# Relay_IO.net
KiCad netlist of a schematic drawn in Altium Designer
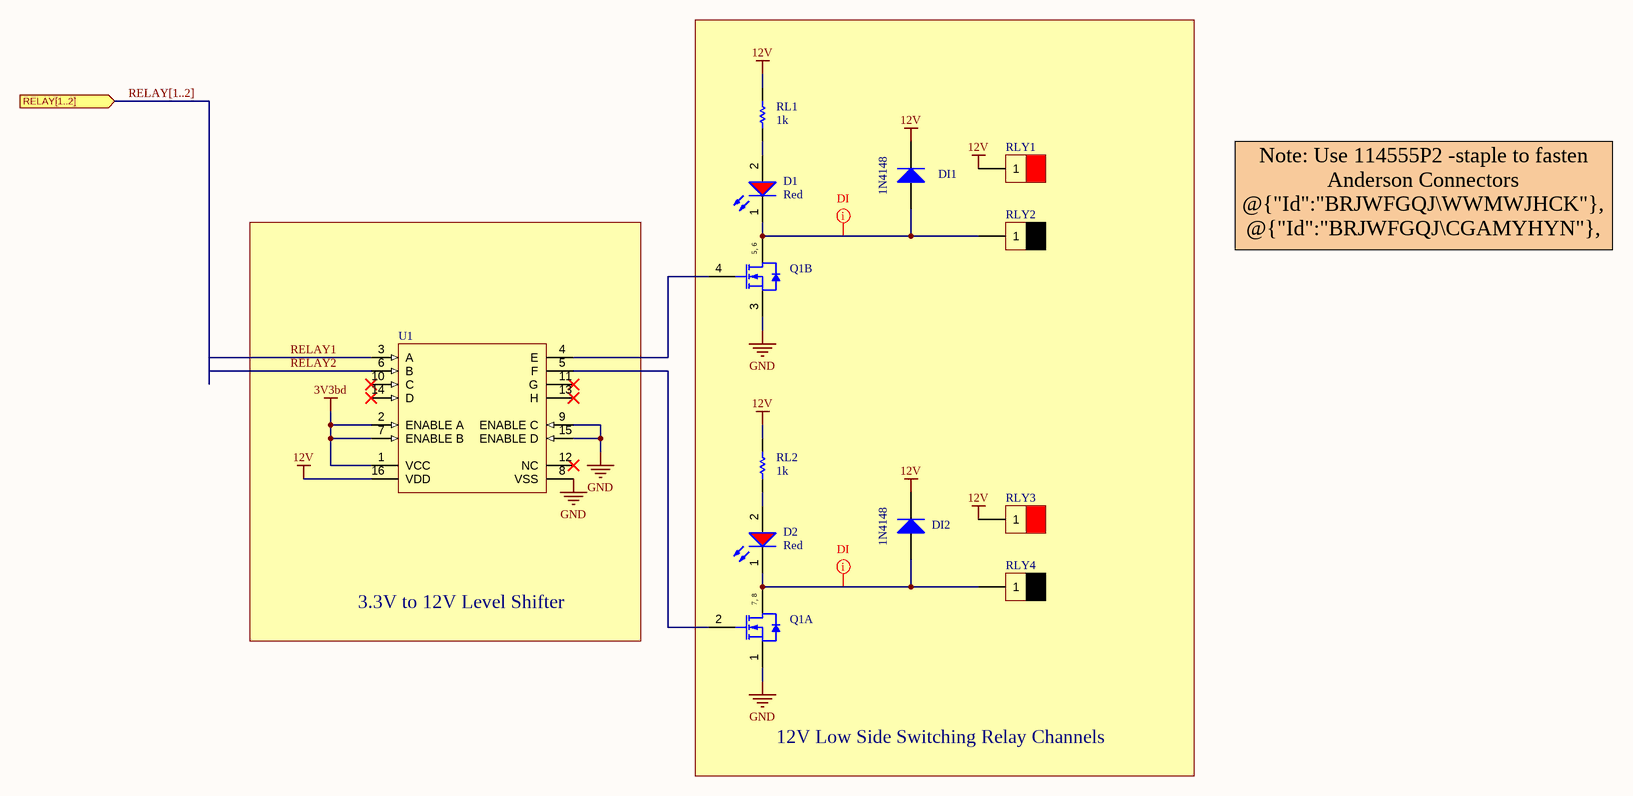
[diagram p0: Relay_IO.SchDoc]

(export (version "E")
  (design (tool "Eeschema 10.0.6"))
  (components
    (comp (ref "D1")
      (value "LED_Red0603")
      (footprint "0603_A")
      (description "Single Color LED, Red, Water Clear, 1.1mm")
      (fields (field (name "COLOR") "Red"))
      (libsource (lib "Advanced] Training Course - A365") (part "LED_Red_2A-1K"))
    )
    (comp (ref "D2")
      (value "LED_Red0603")
      (footprint "0603_A")
      (description "Single Color LED, Red, Water Clear, 1.1mm")
      (fields (field (name "COLOR") "Red"))
      (libsource (lib "Advanced] Training Course - A365") (part "LED_Red_2A-1K"))
    )
    (comp (ref "DI1")
      (value "1N4148")
      (footprint "DO-41")
      (description "Rectifier Diode, 1 Phase, 1 Element, 1A, 100V V(RRM), Silicon, DO-41")
      (libsource (lib "Advanced] Training Course - A365") (part "Diode  General"))
    )
    (comp (ref "DI2")
      (value "1N4148")
      (footprint "DO-41")
      (description "Rectifier Diode, 1 Phase, 1 Element, 1A, 100V V(RRM), Silicon, DO-41")
      (libsource (lib "Advanced] Training Course - A365") (part "Diode  General"))
    )
    (comp (ref "Q1")
      (value "NTHD4508NT1")
      (footprint "ONSC-CHIPFET-8-1206A-03_S2_V")
      (description "Small Signal Field-Effect Transistor")
      (libsource (lib "Advanced] Training Course - A365") (part "MOSFET Dual N-Channel"))
    )
    (comp (ref "RL1")
      (value "Res1K_0805")
      (footprint "0805_L")
      (fields
        (field (name "MANUFACTURER") "Panasonic Electronic Components")
        (field (name "MANUFACTURER PART NUMBER") "ERJ-6GEYJ102V")
        (field (name "RESISTANCE (OHMS)") "1k")
        (field (name "TOLERANCE") "5%")
        (field (name "SOURCE") "WCT.SchLib")
      )
      (libsource (lib "Advanced] Training Course - A365") (part "Resistor General"))
    )
    (comp (ref "RL2")
      (value "Res1K_0805")
      (footprint "0805_L")
      (fields
        (field (name "MANUFACTURER") "Panasonic Electronic Components")
        (field (name "MANUFACTURER PART NUMBER") "ERJ-6GEYJ102V")
        (field (name "RESISTANCE (OHMS)") "1k")
        (field (name "TOLERANCE") "5%")
        (field (name "SOURCE") "WCT.SchLib")
      )
      (libsource (lib "Advanced] Training Course - A365") (part "Resistor General"))
    )
    (comp (ref "RLY1")
      (value "Anderson-1Pin RED_PCB_RHT")
      (footprint "Anderson_RED_RHT_BOT")
      (description "Connector Accessory, Contact, Copper Alloy")
      (libsource (lib "TC - Altium Essentials Course A365 13") (part "Anderson-1Pin RED_PCB_RHT"))
    )
    (comp (ref "RLY2")
      (value "Anderson-1Pin BLK_PCB_RHT")
      (footprint "Anderson_BLK_RHT_BOT")
      (description "Connector Accessory, Contact, Copper Alloy")
      (libsource (lib "Advanced] Training Course - A365") (part "Anderson-1Pin BLK_PCB_RHT"))
    )
    (comp (ref "RLY3")
      (value "Anderson-1Pin RED_PCB_RHT")
      (footprint "Anderson_RED_RHT_BOT")
      (description "Connector Accessory, Contact, Copper Alloy")
      (libsource (lib "TC - Altium Essentials Course A365 13") (part "Anderson-1Pin RED_PCB_RHT"))
    )
    (comp (ref "RLY4")
      (value "Anderson-1Pin BLK_PCB_RHT")
      (footprint "Anderson_BLK_RHT_BOT")
      (description "Connector Accessory, Contact, Copper Alloy")
      (libsource (lib "Advanced] Training Course - A365") (part "Anderson-1Pin BLK_PCB_RHT"))
    )
    (comp (ref "U1")
      (value "CD40109BPW")
      (footprint "PW0016A_M")
      (fields
        (field (name "MANUFACTURER") "Texas Instruments")
        (field (name "MANUFACTURER PART NUMBER") "CD40109BPWR")
        (field (name "AVAILABLE PREVIEW IMAGES") "2D")
        (field (name "SOURCE") "WCT.SchLib")
      )
      (libsource (lib "Advanced] Training Course - A365") (part "CD40109BPW"))
    )
  )
  (nets
    (net (code "1") (name "/RELAY1") (class "Default")
      (node (ref "U1") (pin "3") (pinfunction "A_3") (pintype "input"))
    )
    (net (code "2") (name "/RELAY2") (class "Default")
      (node (ref "U1") (pin "6") (pinfunction "B_6") (pintype "input"))
    )
    (net (code "4") (name "3V3bd") (class "Default")
      (node (ref "U1") (pin "1") (pinfunction "VCC_1") (pintype "power_in"))
      (node (ref "U1") (pin "2") (pinfunction "ENABLE_A_2") (pintype "input"))
      (node (ref "U1") (pin "7") (pinfunction "ENABLE_B_7") (pintype "input"))
    )
    (net (code "5") (name "12V") (class "Default")
      (node (ref "DI1") (pin "2") (pinfunction "K_2") (pintype "passive"))
      (node (ref "DI2") (pin "2") (pinfunction "K_2") (pintype "passive"))
      (node (ref "RL1") (pin "2") (pinfunction "2_2") (pintype "passive"))
      (node (ref "RL2") (pin "2") (pinfunction "2_2") (pintype "passive"))
      (node (ref "RLY1") (pin "1") (pinfunction "1_1") (pintype "passive"))
      (node (ref "RLY3") (pin "1") (pinfunction "1_1") (pintype "passive"))
      (node (ref "U1") (pin "16") (pinfunction "VDD_16") (pintype "power_in"))
    )
    (net (code "6") (name "GND") (class "Default")
      (node (ref "Q1") (pin "1") (pinfunction "S1_1") (pintype "passive"))
      (node (ref "Q1") (pin "3") (pinfunction "S2_3") (pintype "passive"))
      (node (ref "U1") (pin "15") (pinfunction "ENABLE_D_15") (pintype "input"))
      (node (ref "U1") (pin "8") (pinfunction "VSS_8") (pintype "power_in"))
      (node (ref "U1") (pin "9") (pinfunction "ENABLE_C_9") (pintype "input"))
    )
    (net (code "7") (name "Net-(D1-A)") (class "Default")
      (node (ref "D1") (pin "2") (pinfunction "A_2") (pintype "passive"))
      (node (ref "RL1") (pin "1") (pinfunction "1_1") (pintype "passive"))
    )
    (net (code "8") (name "Net-(D1-K)") (class "Default")
      (node (ref "D1") (pin "1") (pinfunction "K_1") (pintype "passive"))
      (node (ref "DI1") (pin "1") (pinfunction "A_1") (pintype "passive"))
      (node (ref "Q1") (pin "5") (pinfunction "D2_5") (pintype "passive"))
      (node (ref "Q1") (pin "6") (pinfunction "D2_6") (pintype "passive"))
      (node (ref "RLY2") (pin "1") (pinfunction "1_1") (pintype "passive"))
    )
    (net (code "9") (name "Net-(D2-A)") (class "Default")
      (node (ref "D2") (pin "2") (pinfunction "A_2") (pintype "passive"))
      (node (ref "RL2") (pin "1") (pinfunction "1_1") (pintype "passive"))
    )
    (net (code "10") (name "Net-(D2-K)") (class "Default")
      (node (ref "D2") (pin "1") (pinfunction "K_1") (pintype "passive"))
      (node (ref "DI2") (pin "1") (pinfunction "A_1") (pintype "passive"))
      (node (ref "Q1") (pin "7") (pinfunction "D1_7") (pintype "passive"))
      (node (ref "Q1") (pin "8") (pinfunction "D1_8") (pintype "passive"))
      (node (ref "RLY4") (pin "1") (pinfunction "1_1") (pintype "passive"))
    )
    (net (code "11") (name "Net-(Q1A-G1)") (class "Default")
      (node (ref "Q1") (pin "2") (pinfunction "G1_2") (pintype "passive"))
      (node (ref "U1") (pin "5") (pinfunction "F_5") (pintype "tri_state"))
    )
    (net (code "12") (name "Net-(Q1B-G2)") (class "Default")
      (node (ref "Q1") (pin "4") (pinfunction "G2_4") (pintype "passive"))
      (node (ref "U1") (pin "4") (pinfunction "E_4") (pintype "tri_state"))
    )
    (net (code "13") (name "unconnected-(U1-C-Pad10)") (class "Default")
      (node (ref "U1") (pin "10") (pinfunction "C_10") (pintype "input+no_connect"))
    )
    (net (code "14") (name "unconnected-(U1-D-Pad14)") (class "Default")
      (node (ref "U1") (pin "14") (pinfunction "D_14") (pintype "input+no_connect"))
    )
    (net (code "15") (name "unconnected-(U1-G-Pad11)") (class "Default")
      (node (ref "U1") (pin "11") (pinfunction "G_11") (pintype "tri_state+no_connect"))
    )
    (net (code "16") (name "unconnected-(U1-H-Pad13)") (class "Default")
      (node (ref "U1") (pin "13") (pinfunction "H_13") (pintype "tri_state+no_connect"))
    )
    (net (code "17") (name "unconnected-(U1-NC-Pad12)") (class "Default")
      (node (ref "U1") (pin "12") (pinfunction "NC_12") (pintype "passive+no_connect"))
    )
  )
)
